# Proiect2026Hagi.net
KiCad netlist of a schematic drawn in EAGLE
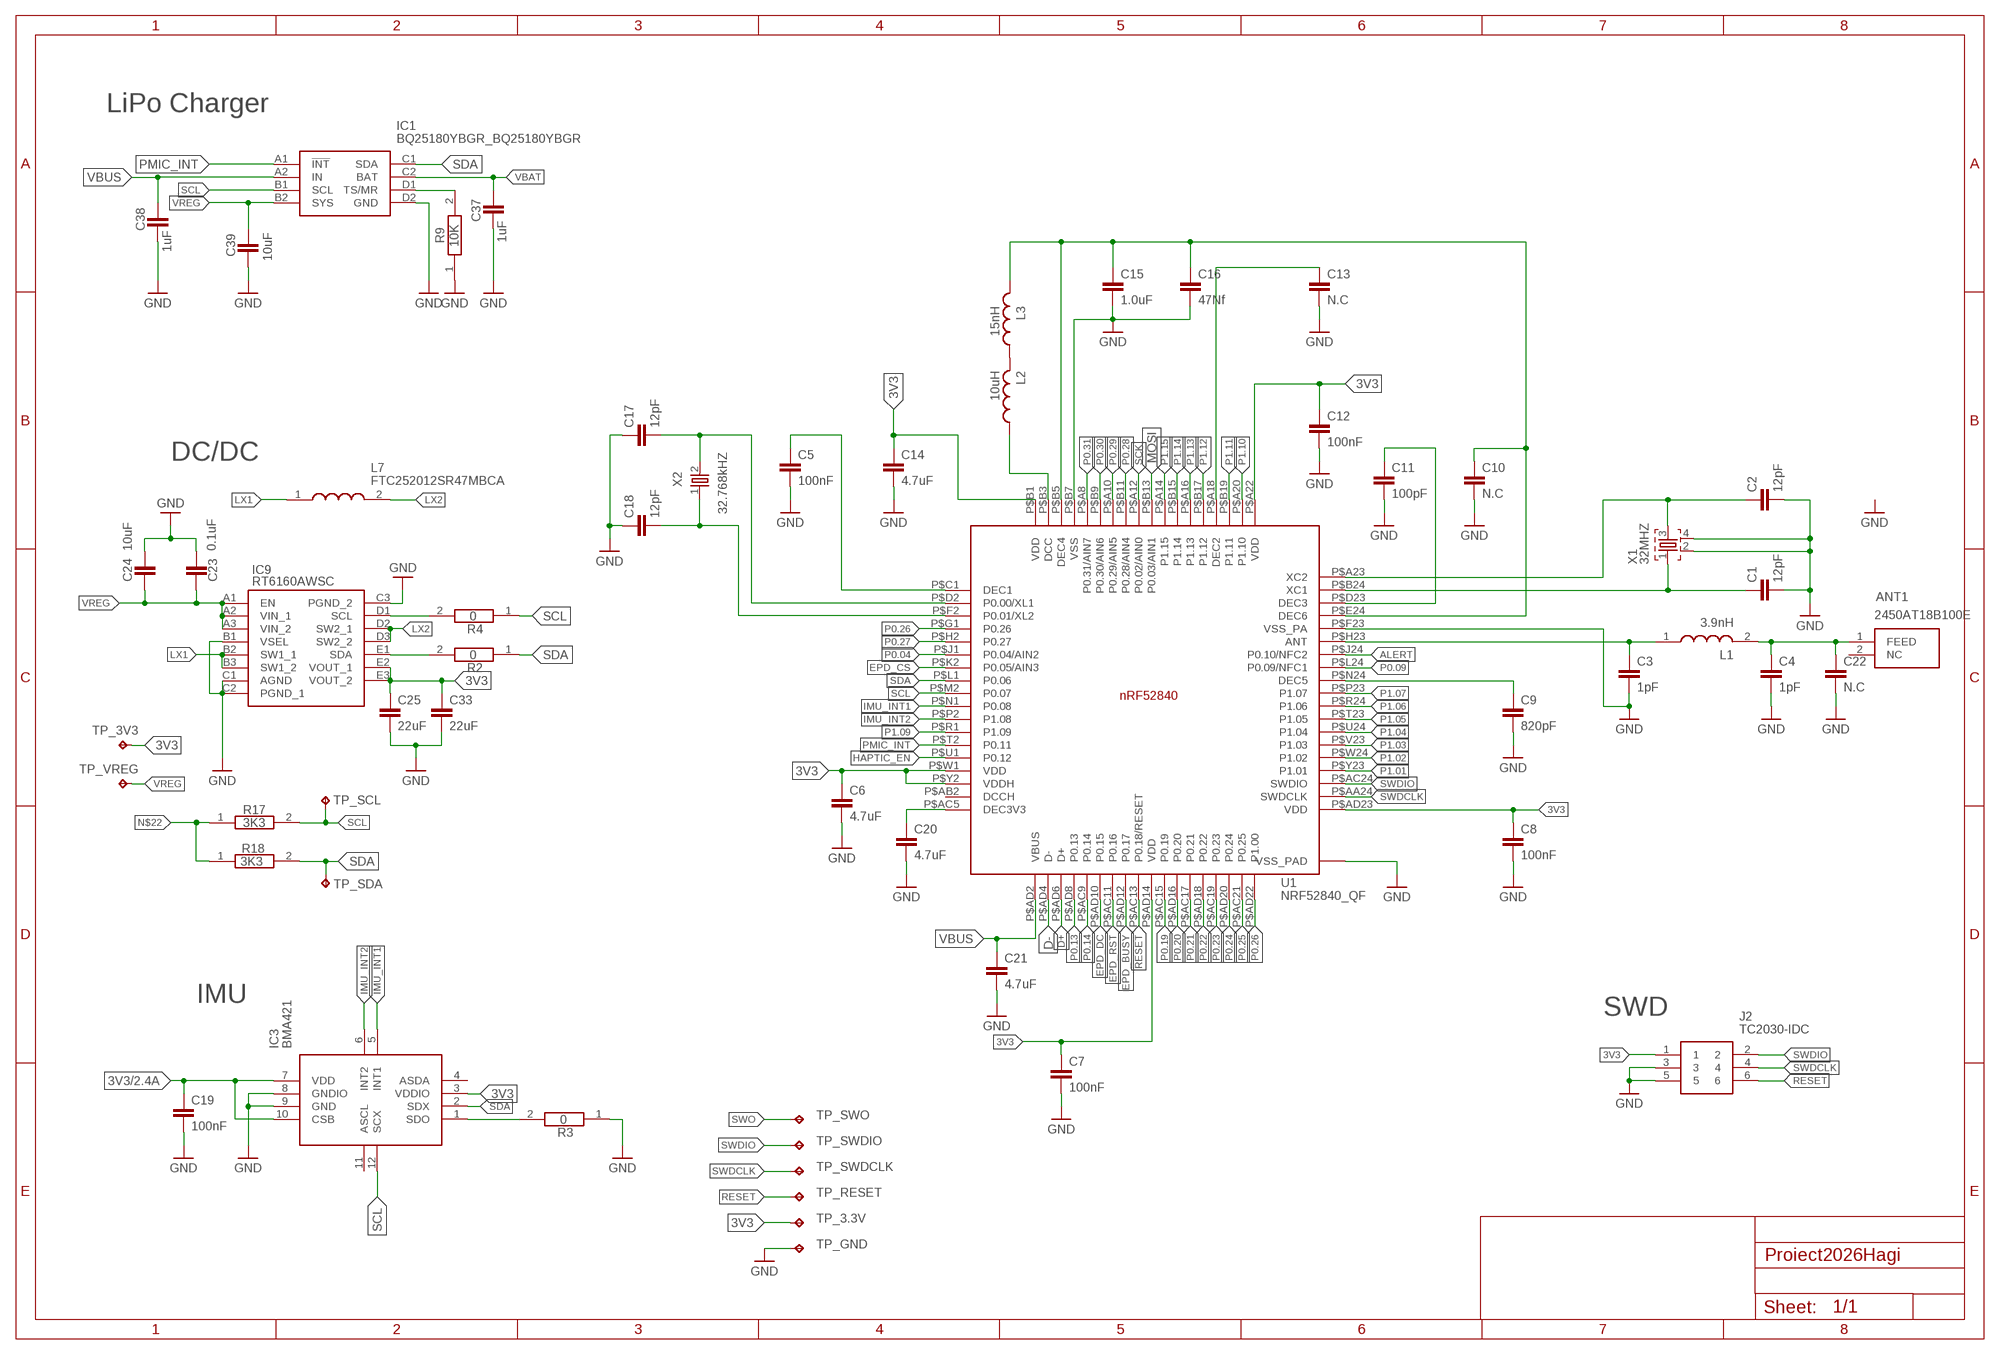
[diagram p0: schematic, sheet 1, part 1 of 2]
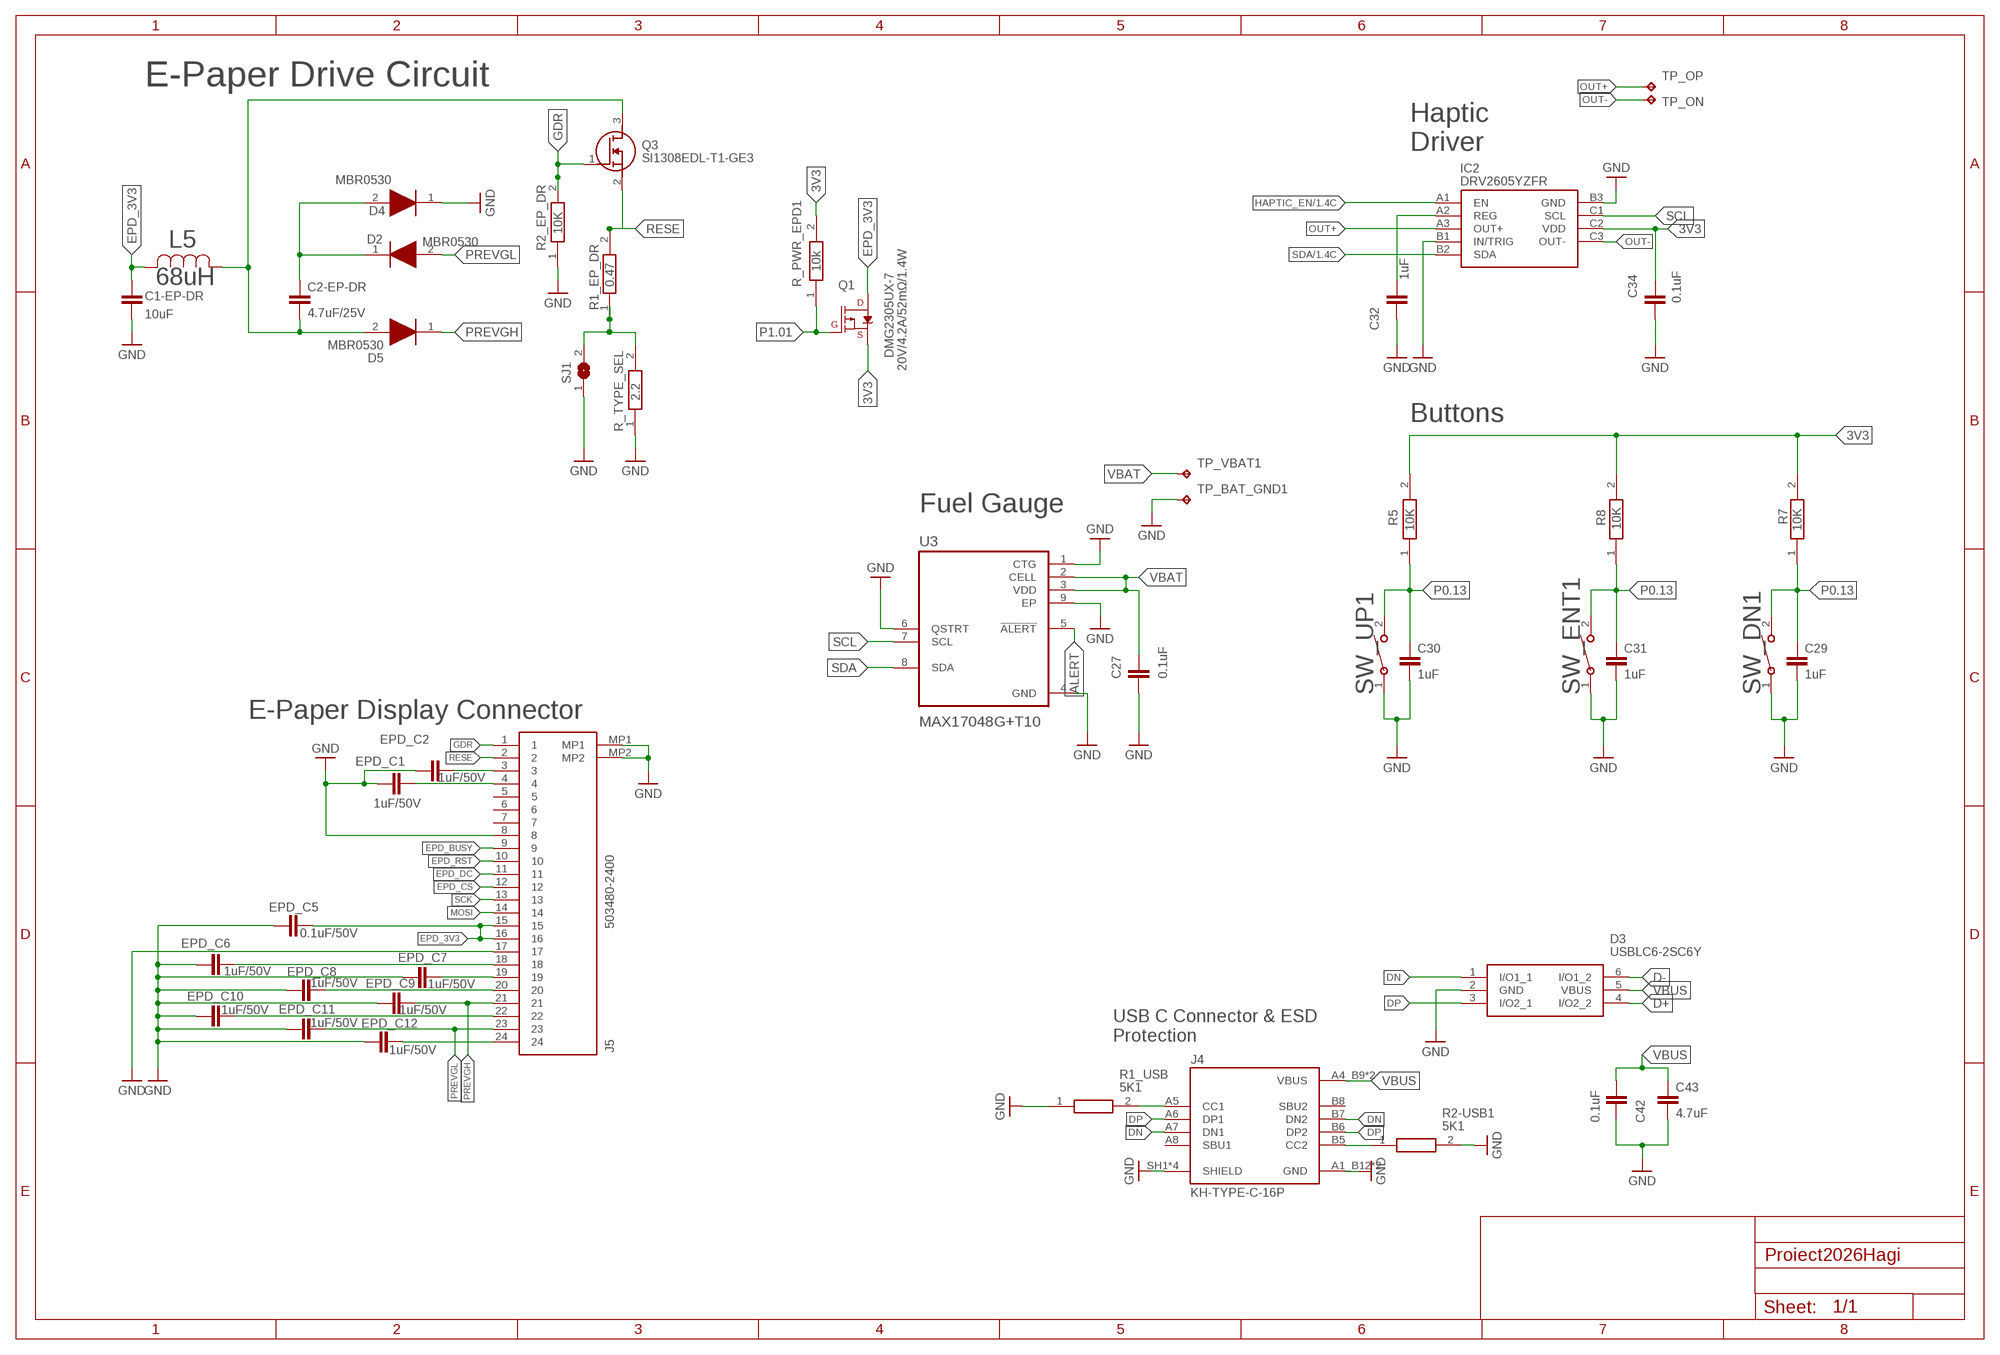
[diagram p1: schematic, sheet 1, part 2 of 2]

(export (version "E")
  (design (tool "Eeschema 10.0.6"))
  (components
    (comp (ref "ANT1")
      (value "2450AT18B100E")
      (footprint "eagle-import:2450AT18B100E_ANTC3216X140N")
      (fields (field (name "MOUSER_PART_NUMBER") "609-2450AT18B100E"))
      (libsource (lib "eagle-import") (part "2450AT18B100E_2450AT18B100E"))
    )
    (comp (ref "C1")
      (value "12pF")
      (footprint "eagle-import:NORDIC_NRF_3_RESC0201_L")
      (libsource (lib "eagle-import") (part "NORDIC_NRF_3_CAPACITOR_0201_L"))
    )
    (comp (ref "C1-EP-DR")
      (value "10uF")
      (footprint "eagle-import:NORDIC_NRF_3_RESC0402_L")
      (libsource (lib "eagle-import") (part "NORDIC_NRF_3_CAPACITOR_0402_L"))
    )
    (comp (ref "C2")
      (value "12pF")
      (footprint "eagle-import:NORDIC_NRF_3_RESC0201_L")
      (libsource (lib "eagle-import") (part "NORDIC_NRF_3_CAPACITOR_0201_L"))
    )
    (comp (ref "C2-EP-DR")
      (value "4.7uF/25V")
      (footprint "eagle-import:NORDIC_NRF_3_RESC0402_L")
      (libsource (lib "eagle-import") (part "NORDIC_NRF_3_CAPACITOR_0402_L"))
    )
    (comp (ref "C3")
      (value "1pF")
      (footprint "eagle-import:NORDIC_NRF_3_RESC0201_L")
      (libsource (lib "eagle-import") (part "NORDIC_NRF_3_CAPACITOR_0201_L"))
    )
    (comp (ref "C4")
      (value "1pF")
      (footprint "eagle-import:NORDIC_NRF_3_RESC0201_L")
      (libsource (lib "eagle-import") (part "NORDIC_NRF_3_CAPACITOR_0201_L"))
    )
    (comp (ref "C5")
      (value "100nF")
      (footprint "eagle-import:NORDIC_NRF_3_RESC0201_L")
      (libsource (lib "eagle-import") (part "NORDIC_NRF_3_CAPACITOR_0201_L"))
    )
    (comp (ref "C6")
      (value "4.7uF")
      (footprint "eagle-import:NORDIC_NRF_3_RESC0402_L")
      (libsource (lib "eagle-import") (part "NORDIC_NRF_3_CAPACITOR_0402_L"))
    )
    (comp (ref "C7")
      (value "100nF")
      (footprint "eagle-import:NORDIC_NRF_3_RESC0201_L")
      (libsource (lib "eagle-import") (part "NORDIC_NRF_3_CAPACITOR_0201_L"))
    )
    (comp (ref "C8")
      (value "100nF")
      (footprint "eagle-import:NORDIC_NRF_3_RESC0201_L")
      (libsource (lib "eagle-import") (part "NORDIC_NRF_3_CAPACITOR_0201_L"))
    )
    (comp (ref "C9")
      (value "820pF")
      (footprint "eagle-import:NORDIC_NRF_3_RESC0201_L")
      (libsource (lib "eagle-import") (part "NORDIC_NRF_3_CAPACITOR_0201_L"))
    )
    (comp (ref "C10")
      (value "N.C")
      (footprint "eagle-import:NORDIC_NRF_3_RESC0201_L")
      (libsource (lib "eagle-import") (part "NORDIC_NRF_3_CAPACITOR_0201_L"))
    )
    (comp (ref "C11")
      (value "100pF")
      (footprint "eagle-import:NORDIC_NRF_3_RESC0201_L")
      (libsource (lib "eagle-import") (part "NORDIC_NRF_3_CAPACITOR_0201_L"))
    )
    (comp (ref "C12")
      (value "100nF")
      (footprint "eagle-import:NORDIC_NRF_3_RESC0201_L")
      (libsource (lib "eagle-import") (part "NORDIC_NRF_3_CAPACITOR_0201_L"))
    )
    (comp (ref "C13")
      (value "N.C")
      (footprint "eagle-import:NORDIC_NRF_3_RESC0201_L")
      (libsource (lib "eagle-import") (part "NORDIC_NRF_3_CAPACITOR_0201_L"))
    )
    (comp (ref "C14")
      (value "4.7uF")
      (footprint "eagle-import:NORDIC_NRF_3_RESC0402_L")
      (libsource (lib "eagle-import") (part "NORDIC_NRF_3_CAPACITOR_0402_L"))
    )
    (comp (ref "C15")
      (value "1.0uF")
      (footprint "eagle-import:NORDIC_NRF_3_RESC0402_L")
      (libsource (lib "eagle-import") (part "NORDIC_NRF_3_CAPACITOR_0402_L"))
    )
    (comp (ref "C16")
      (value "47Nf")
      (footprint "eagle-import:NORDIC_NRF_3_RESC0201_L")
      (libsource (lib "eagle-import") (part "NORDIC_NRF_3_CAPACITOR_0201_L"))
    )
    (comp (ref "C17")
      (value "12pF")
      (footprint "eagle-import:NORDIC_NRF_3_RESC0201_L")
      (libsource (lib "eagle-import") (part "NORDIC_NRF_3_CAPACITOR_0201_L"))
    )
    (comp (ref "C18")
      (value "12pF")
      (footprint "eagle-import:NORDIC_NRF_3_RESC0201_L")
      (libsource (lib "eagle-import") (part "NORDIC_NRF_3_CAPACITOR_0201_L"))
    )
    (comp (ref "C19")
      (value "100nF")
      (footprint "eagle-import:NORDIC_NRF_3_RESC0201_L")
      (libsource (lib "eagle-import") (part "NORDIC_NRF_3_CAPACITOR_0201_L"))
    )
    (comp (ref "C20")
      (value "4.7uF")
      (footprint "eagle-import:NORDIC_NRF_3_RESC0402_L")
      (libsource (lib "eagle-import") (part "NORDIC_NRF_3_CAPACITOR_0402_L"))
    )
    (comp (ref "C21")
      (value "4.7uF")
      (footprint "eagle-import:NORDIC_NRF_3_RESC0402_L")
      (libsource (lib "eagle-import") (part "NORDIC_NRF_3_CAPACITOR_0402_L"))
    )
    (comp (ref "C22")
      (value "N.C")
      (footprint "eagle-import:NORDIC_NRF_3_RESC0201_L")
      (libsource (lib "eagle-import") (part "NORDIC_NRF_3_CAPACITOR_0201_L"))
    )
    (comp (ref "C23")
      (value "0.1uF")
      (footprint "eagle-import:NORDIC_NRF_3_RESC0402_L")
      (libsource (lib "eagle-import") (part "NORDIC_NRF_3_CAPACITOR_0402_L"))
    )
    (comp (ref "C24")
      (value "10uF")
      (footprint "eagle-import:NORDIC_NRF_3_RESC0201_L")
      (libsource (lib "eagle-import") (part "NORDIC_NRF_3_CAPACITOR_0201_L"))
    )
    (comp (ref "C25")
      (value "22uF")
      (footprint "eagle-import:NORDIC_NRF_3_RESC0402_L")
      (libsource (lib "eagle-import") (part "NORDIC_NRF_3_CAPACITOR_0402_L"))
    )
    (comp (ref "C27")
      (value "0.1uF")
      (footprint "eagle-import:NORDIC_NRF_3_RESC0201_L")
      (libsource (lib "eagle-import") (part "NORDIC_NRF_3_CAPACITOR_0201_L"))
    )
    (comp (ref "C29")
      (value "1uF")
      (footprint "eagle-import:NORDIC_NRF_3_RESC0402_L")
      (libsource (lib "eagle-import") (part "NORDIC_NRF_3_CAPACITOR_0402_L"))
    )
    (comp (ref "C30")
      (value "1uF")
      (footprint "eagle-import:NORDIC_NRF_3_RESC0402_L")
      (libsource (lib "eagle-import") (part "NORDIC_NRF_3_CAPACITOR_0402_L"))
    )
    (comp (ref "C31")
      (value "1uF")
      (footprint "eagle-import:NORDIC_NRF_3_RESC0402_L")
      (libsource (lib "eagle-import") (part "NORDIC_NRF_3_CAPACITOR_0402_L"))
    )
    (comp (ref "C32")
      (value "1uF")
      (footprint "eagle-import:NORDIC_NRF_3_RESC0402_L")
      (libsource (lib "eagle-import") (part "NORDIC_NRF_3_CAPACITOR_0402_L"))
    )
    (comp (ref "C33")
      (value "22uF")
      (footprint "eagle-import:NORDIC_NRF_3_RESC0402_L")
      (libsource (lib "eagle-import") (part "NORDIC_NRF_3_CAPACITOR_0402_L"))
    )
    (comp (ref "C34")
      (value "0.1uF")
      (footprint "eagle-import:NORDIC_NRF_3_RESC0201_L")
      (libsource (lib "eagle-import") (part "NORDIC_NRF_3_CAPACITOR_0201_L"))
    )
    (comp (ref "C37")
      (value "1uF")
      (footprint "eagle-import:PERFECT_0402_0402")
      (libsource (lib "eagle-import") (part "PERFECT_0402_CAP_0402"))
    )
    (comp (ref "C38")
      (value "1uF")
      (footprint "eagle-import:PERFECT_0402_0402")
      (libsource (lib "eagle-import") (part "PERFECT_0402_CAP_0402"))
    )
    (comp (ref "C39")
      (value "10uF")
      (footprint "eagle-import:PERFECT_0402_0402")
      (libsource (lib "eagle-import") (part "PERFECT_0402_CAP_0402"))
    )
    (comp (ref "C42")
      (value "0.1uF")
      (footprint "eagle-import:NORDIC_NRF_3_RESC0201_L")
      (libsource (lib "eagle-import") (part "NORDIC_NRF_3_CAPACITOR_0201_L"))
    )
    (comp (ref "C43")
      (value "4.7uF")
      (footprint "eagle-import:NORDIC_NRF_3_RESC0402_L")
      (libsource (lib "eagle-import") (part "NORDIC_NRF_3_CAPACITOR_0402_L"))
    )
    (comp (ref "D2")
      (value "MBR0530")
      (footprint "eagle-import:ESP32_C6_LIBRARY_5_SOD3716X135N")
      (fields (field (name "MF") "ON Semiconductor"))
      (libsource (lib "eagle-import") (part "ESP32_C6_LIBRARY_5_MBR0530"))
    )
    (comp (ref "D3")
      (value "USBLC6-2SC6Y")
      (footprint "eagle-import:ESP32_C6_LIBRARY_3_SOT95P280X145-6N")
      (fields (field (name "MF") "STMicroelectronics"))
      (libsource (lib "eagle-import") (part "ESP32_C6_LIBRARY_3_USBLC6-2SC6Y"))
    )
    (comp (ref "D4")
      (value "MBR0530")
      (footprint "eagle-import:ESP32_C6_LIBRARY_5_SOD3716X135N")
      (fields (field (name "MF") "ON Semiconductor"))
      (libsource (lib "eagle-import") (part "ESP32_C6_LIBRARY_5_MBR0530"))
    )
    (comp (ref "D5")
      (value "MBR0530")
      (footprint "eagle-import:ESP32_C6_LIBRARY_5_SOD3716X135N")
      (fields (field (name "MF") "ON Semiconductor"))
      (libsource (lib "eagle-import") (part "ESP32_C6_LIBRARY_5_MBR0530"))
    )
    (comp (ref "EPD_C1")
      (value "1uF/50V")
      (footprint "eagle-import:NORDIC_NRF_3_RESC0402_L")
      (libsource (lib "eagle-import") (part "NORDIC_NRF_3_CAPACITOR_0402_L"))
    )
    (comp (ref "EPD_C2")
      (value "1uF/50V")
      (footprint "eagle-import:NORDIC_NRF_3_RESC0402_L")
      (libsource (lib "eagle-import") (part "NORDIC_NRF_3_CAPACITOR_0402_L"))
    )
    (comp (ref "EPD_C5")
      (value "0.1uF/50V")
      (footprint "eagle-import:NORDIC_NRF_3_RESC0201_L")
      (libsource (lib "eagle-import") (part "NORDIC_NRF_3_CAPACITOR_0201_L"))
    )
    (comp (ref "EPD_C6")
      (value "1uF/50V")
      (footprint "eagle-import:NORDIC_NRF_3_RESC0402_L")
      (libsource (lib "eagle-import") (part "NORDIC_NRF_3_CAPACITOR_0402_L"))
    )
    (comp (ref "EPD_C7")
      (value "1uF/50V")
      (footprint "eagle-import:NORDIC_NRF_3_RESC0402_L")
      (libsource (lib "eagle-import") (part "NORDIC_NRF_3_CAPACITOR_0402_L"))
    )
    (comp (ref "EPD_C8")
      (value "1uF/50V")
      (footprint "eagle-import:NORDIC_NRF_3_RESC0402_L")
      (libsource (lib "eagle-import") (part "NORDIC_NRF_3_CAPACITOR_0402_L"))
    )
    (comp (ref "EPD_C9")
      (value "1uF/50V")
      (footprint "eagle-import:NORDIC_NRF_3_RESC0402_L")
      (libsource (lib "eagle-import") (part "NORDIC_NRF_3_CAPACITOR_0402_L"))
    )
    (comp (ref "EPD_C10")
      (value "1uF/50V")
      (footprint "eagle-import:NORDIC_NRF_3_RESC0402_L")
      (libsource (lib "eagle-import") (part "NORDIC_NRF_3_CAPACITOR_0402_L"))
    )
    (comp (ref "EPD_C11")
      (value "1uF/50V")
      (footprint "eagle-import:NORDIC_NRF_3_RESC0402_L")
      (libsource (lib "eagle-import") (part "NORDIC_NRF_3_CAPACITOR_0402_L"))
    )
    (comp (ref "EPD_C12")
      (value "1uF/50V")
      (footprint "eagle-import:NORDIC_NRF_3_RESC0402_L")
      (libsource (lib "eagle-import") (part "NORDIC_NRF_3_CAPACITOR_0402_L"))
    )
    (comp (ref "IC1")
      (value "BQ25180YBGR_BQ25180YBGR")
      (footprint "eagle-import:BQ25180YBGR_BGA8C40P2X4_100X155X50")
      (fields
        (field (name "ARROW_PART_NUMBER") "BQ25180YBGR")
        (field (name "MOUSER_PART_NUMBER") "595-BQ25180YBGR")
      )
      (libsource (lib "eagle-import") (part "BQ25180YBGR_BQ25180YBGR"))
    )
    (comp (ref "IC2")
      (value "DRV2605YZFR")
      (footprint "eagle-import:DRV2605YZFR_BGA9C50P3X3_144X144X62")
      (libsource (lib "eagle-import") (part "DRV2605YZFR_DRV2605YZFR"))
    )
    (comp (ref "IC3")
      (value "BMA421")
      (footprint "eagle-import:BMA423_BMA423")
      (fields (field (name "ARROW_PART_NUMBER") "BMA423") (field (name "MOUSER_PART_NUMBER") "262-BMA423"))
      (libsource (lib "eagle-import") (part "BMA423_BMA423"))
    )
    (comp (ref "IC9")
      (value "RT6160AWSC")
      (footprint "eagle-import:RT6160AWSC_BGA15C40P3X5_140X230X60")
      (fields (field (name "MOUSER_PART_NUMBER") "835-RT6160AWSC"))
      (libsource (lib "eagle-import") (part "RT6160AWSC_RT6160AWSC"))
    )
    (comp (ref "J2")
      (value "TC2030-IDC")
      (footprint "eagle-import:TC2030-IDC_TC2030IDC")
      (libsource (lib "eagle-import") (part "TC2030-IDC_TC2030-IDC"))
    )
    (comp (ref "J4")
      (value "KH-TYPE-C-16P")
      (footprint "eagle-import:KH-TYPE-C-16P_KINGHELM_KH-TYPE-C-16P")
      (fields (field (name "MF") "kinghelm"))
      (libsource (lib "eagle-import") (part "KH-TYPE-C-16P_KH-TYPE-C-16P"))
    )
    (comp (ref "J5")
      (value "503480-2400")
      (footprint "eagle-import:503480-2400_5034802400")
      (fields (field (name "MOUSER_PART_NUMBER") "538-503480-2400"))
      (libsource (lib "eagle-import") (part "503480-2400_503480-2400"))
    )
    (comp (ref "L1")
      (value "3.9nH")
      (footprint "eagle-import:MLP2016SR47MT0S1_INDC2016X100N")
      (fields (field (name "MANUFACTURER_PART_NUMBER") "FTC252012SR47MBCA"))
      (libsource (lib "eagle-import") (part "MLP2016SR47MT0S1_FTC252012SR47MBCA"))
    )
    (comp (ref "L2")
      (value "10uH")
      (footprint "eagle-import:NORDIC_NRF_2_RESC0402_L")
      (libsource (lib "eagle-import") (part "NORDIC_NRF_2_INDUCTOR_0402_L"))
    )
    (comp (ref "L3")
      (value "15nH")
      (footprint "eagle-import:NORDIC_NRF_2_RESC0402_L")
      (libsource (lib "eagle-import") (part "NORDIC_NRF_2_INDUCTOR_0402_L"))
    )
    (comp (ref "L5")
      (value "68uH")
      (footprint "eagle-import:ESP32_C6_LIBRARY_2_IND_4828-WE-TPC_WRE")
      (fields
        (field (name "MANUFACTURER_PART_NUMBER") "744043680")
        (field (name "COPYRIGHT") "Copyright (C) 2024 Ultra Librarian. All rights reserved.")
      )
      (libsource (lib "eagle-import") (part "ESP32_C6_LIBRARY_2_744043680IND_4828-WE-TPC_WRE"))
    )
    (comp (ref "L7")
      (value "FTC252012SR47MBCA")
      (footprint "eagle-import:MLP2016SR47MT0S1_INDC2016X100N")
      (libsource (lib "eagle-import") (part "MLP2016SR47MT0S1_FTC252012SR47MBCA"))
    )
    (comp (ref "Q1")
      (value "20V/4.2A/52mΩ/1.4W")
      (footprint "eagle-import:ESP32_C6_LIBRARY_4_ESP32_C6_LIBRARY_4_ESP32_C6_LIBRARY_4_ESP32_C6_LIBRARY_4_ESP32_WROVER_SPARKFUN-DISCRETESEMI_SOT23-3")
      (libsource (lib "eagle-import") (part "ESP32_C6_LIBRARY_4_ESP32_WROVER_SPARKFUN-DISCRETESEMI_MOSFET_PCH-DMG2305UX-7"))
    )
    (comp (ref "Q3")
      (value "SI1308EDL-T1-GE3")
      (footprint "eagle-import:ESP32_C6_LIBRARY_6_SOT65P210X110-3N")
      (fields (field (name "MF") "Vishay Siliconix"))
      (libsource (lib "eagle-import") (part "ESP32_C6_LIBRARY_6_SI1308EDL-T1-GE3"))
    )
    (comp (ref "R1_EP_DR")
      (value "0.47")
      (footprint "eagle-import:CPF0201D7K68C1_0201")
      (libsource (lib "eagle-import") (part "CPF0201D7K68C1_CPF0201D7K68C1"))
    )
    (comp (ref "R1_USB")
      (value "5K1")
      (footprint "eagle-import:CPF0201D7K68C1_0201")
      (libsource (lib "eagle-import") (part "CPF0201D7K68C1_CPF0201D7K68C1"))
    )
    (comp (ref "R2")
      (value "0")
      (footprint "eagle-import:CPF0201D7K68C1_0201")
      (libsource (lib "eagle-import") (part "CPF0201D7K68C1_CPF0201D7K68C1"))
    )
    (comp (ref "R2-USB1")
      (value "5K1")
      (footprint "eagle-import:CPF0201D7K68C1_0201")
      (libsource (lib "eagle-import") (part "CPF0201D7K68C1_CPF0201D7K68C1"))
    )
    (comp (ref "R2_EP_DR")
      (value "10K")
      (footprint "eagle-import:CPF0201D7K68C1_0201")
      (libsource (lib "eagle-import") (part "CPF0201D7K68C1_CPF0201D7K68C1"))
    )
    (comp (ref "R3")
      (value "0")
      (footprint "eagle-import:CPF0201D7K68C1_0201")
      (libsource (lib "eagle-import") (part "CPF0201D7K68C1_CPF0201D7K68C1"))
    )
    (comp (ref "R4")
      (value "0")
      (footprint "eagle-import:CPF0201D7K68C1_0201")
      (libsource (lib "eagle-import") (part "CPF0201D7K68C1_CPF0201D7K68C1"))
    )
    (comp (ref "R5")
      (value "10K")
      (footprint "eagle-import:CPF0201D7K68C1_0201")
      (libsource (lib "eagle-import") (part "CPF0201D7K68C1_CPF0201D7K68C1"))
    )
    (comp (ref "R7")
      (value "10K")
      (footprint "eagle-import:CPF0201D7K68C1_0201")
      (libsource (lib "eagle-import") (part "CPF0201D7K68C1_CPF0201D7K68C1"))
    )
    (comp (ref "R8")
      (value "10K")
      (footprint "eagle-import:CPF0201D7K68C1_0201")
      (libsource (lib "eagle-import") (part "CPF0201D7K68C1_CPF0201D7K68C1"))
    )
    (comp (ref "R9")
      (value "10K")
      (footprint "eagle-import:CPF0201D7K68C1_0201")
      (libsource (lib "eagle-import") (part "CPF0201D7K68C1_CPF0201D7K68C1"))
    )
    (comp (ref "R17")
      (value "3K3")
      (footprint "eagle-import:CPF0201D7K68C1_0201")
      (libsource (lib "eagle-import") (part "CPF0201D7K68C1_CPF0201D7K68C1"))
    )
    (comp (ref "R18")
      (value "3K3")
      (footprint "eagle-import:CPF0201D7K68C1_0201")
      (libsource (lib "eagle-import") (part "CPF0201D7K68C1_CPF0201D7K68C1"))
    )
    (comp (ref "R_PWR_EPD1")
      (value "10k")
      (footprint "eagle-import:CPF0201D7K68C1_0201")
      (libsource (lib "eagle-import") (part "CPF0201D7K68C1_CPF0201D7K68C1"))
    )
    (comp (ref "R_TYPE_SEL")
      (value "2.2")
      (footprint "eagle-import:CPF0201D7K68C1_0201")
      (libsource (lib "eagle-import") (part "CPF0201D7K68C1_CPF0201D7K68C1"))
    )
    (comp (ref "SJ1")
      (value "ESP32_C6_LIBRARY_7_JUMPER_SJ")
      (footprint "eagle-import:ESP32_C6_LIBRARY_7_JUMPER_SJ")
      (libsource (lib "eagle-import") (part "ESP32_C6_LIBRARY_7_JUMPER_SJ"))
    )
    (comp (ref "SW_DN1")
      (value "2025-10-22_07-23-44_LIBRARY_EVP-AKE31ASW_EVP-AKE31A_PAN")
      (footprint "eagle-import:2025-10-22_07-23-44_LIBRARY_SW_EVP-AKE31A_PAN")
      (fields
        (field (name "MANUFACTURER_PART_NUMBER") "EVP-AKE31A")
        (field (name "COPYRIGHT") "Copyright (C) 2025 Ultra Librarian. All rights reserved.")
      )
      (libsource (lib "eagle-import") (part "2025-10-22_07-23-44_LIBRARY_EVP-AKE31ASW_EVP-AKE31A_PAN"))
    )
    (comp (ref "SW_ENT1")
      (value "2025-10-22_07-23-44_LIBRARY_EVP-AKE31ASW_EVP-AKE31A_PAN")
      (footprint "eagle-import:2025-10-22_07-23-44_LIBRARY_SW_EVP-AKE31A_PAN")
      (fields
        (field (name "MANUFACTURER_PART_NUMBER") "EVP-AKE31A")
        (field (name "COPYRIGHT") "Copyright (C) 2025 Ultra Librarian. All rights reserved.")
      )
      (libsource (lib "eagle-import") (part "2025-10-22_07-23-44_LIBRARY_EVP-AKE31ASW_EVP-AKE31A_PAN"))
    )
    (comp (ref "SW_UP1")
      (value "2025-10-22_07-23-44_LIBRARY_EVP-AKE31ASW_EVP-AKE31A_PAN")
      (footprint "eagle-import:2025-10-22_07-23-44_LIBRARY_SW_EVP-AKE31A_PAN")
      (fields
        (field (name "MANUFACTURER_PART_NUMBER") "EVP-AKE31A")
        (field (name "COPYRIGHT") "Copyright (C) 2025 Ultra Librarian. All rights reserved.")
      )
      (libsource (lib "eagle-import") (part "2025-10-22_07-23-44_LIBRARY_EVP-AKE31ASW_EVP-AKE31A_PAN"))
    )
    (comp (ref "TP_3.3V")
      (value "HECTOR_WATCH_1_TPTP20R")
      (footprint "eagle-import:HECTOR_WATCH_1_TP20R")
      (libsource (lib "eagle-import") (part "HECTOR_WATCH_1_TPTP20R"))
    )
    (comp (ref "TP_3V3")
      (value "HECTOR_WATCH_1_TPTP20R")
      (footprint "eagle-import:HECTOR_WATCH_1_TP20R")
      (libsource (lib "eagle-import") (part "HECTOR_WATCH_1_TPTP20R"))
    )
    (comp (ref "TP_BAT_GND1")
      (value "HECTOR_WATCH_1_TPTP20R")
      (footprint "eagle-import:HECTOR_WATCH_1_TP20R")
      (libsource (lib "eagle-import") (part "HECTOR_WATCH_1_TPTP20R"))
    )
    (comp (ref "TP_GND")
      (value "HECTOR_WATCH_1_TPTP20R")
      (footprint "eagle-import:HECTOR_WATCH_1_TP20R")
      (libsource (lib "eagle-import") (part "HECTOR_WATCH_1_TPTP20R"))
    )
    (comp (ref "TP_ON")
      (value "HECTOR_WATCH_1_TPTP20R")
      (footprint "eagle-import:HECTOR_WATCH_1_TP20R")
      (libsource (lib "eagle-import") (part "HECTOR_WATCH_1_TPTP20R"))
    )
    (comp (ref "TP_OP")
      (value "HECTOR_WATCH_1_TPTP20R")
      (footprint "eagle-import:HECTOR_WATCH_1_TP20R")
      (libsource (lib "eagle-import") (part "HECTOR_WATCH_1_TPTP20R"))
    )
    (comp (ref "TP_RESET")
      (value "HECTOR_WATCH_1_TPTP20R")
      (footprint "eagle-import:HECTOR_WATCH_1_TP20R")
      (libsource (lib "eagle-import") (part "HECTOR_WATCH_1_TPTP20R"))
    )
    (comp (ref "TP_SCL")
      (value "HECTOR_WATCH_1_TPTP20R")
      (footprint "eagle-import:HECTOR_WATCH_1_TP20R")
      (libsource (lib "eagle-import") (part "HECTOR_WATCH_1_TPTP20R"))
    )
    (comp (ref "TP_SDA")
      (value "HECTOR_WATCH_1_TPTP20R")
      (footprint "eagle-import:HECTOR_WATCH_1_TP20R")
      (libsource (lib "eagle-import") (part "HECTOR_WATCH_1_TPTP20R"))
    )
    (comp (ref "TP_SWDCLK")
      (value "HECTOR_WATCH_1_TPTP20R")
      (footprint "eagle-import:HECTOR_WATCH_1_TP20R")
      (libsource (lib "eagle-import") (part "HECTOR_WATCH_1_TPTP20R"))
    )
    (comp (ref "TP_SWDIO")
      (value "HECTOR_WATCH_1_TPTP20R")
      (footprint "eagle-import:HECTOR_WATCH_1_TP20R")
      (libsource (lib "eagle-import") (part "HECTOR_WATCH_1_TPTP20R"))
    )
    (comp (ref "TP_SWO")
      (value "HECTOR_WATCH_1_TPTP20R")
      (footprint "eagle-import:HECTOR_WATCH_1_TP20R")
      (libsource (lib "eagle-import") (part "HECTOR_WATCH_1_TPTP20R"))
    )
    (comp (ref "TP_VBAT1")
      (value "HECTOR_WATCH_1_TPTP20R")
      (footprint "eagle-import:HECTOR_WATCH_1_TP20R")
      (libsource (lib "eagle-import") (part "HECTOR_WATCH_1_TPTP20R"))
    )
    (comp (ref "TP_VREG")
      (value "HECTOR_WATCH_1_TPTP20R")
      (footprint "eagle-import:HECTOR_WATCH_1_TP20R")
      (libsource (lib "eagle-import") (part "HECTOR_WATCH_1_TPTP20R"))
    )
    (comp (ref "U1")
      (value "NRF52840_QF")
      (footprint "eagle-import:NORDIC_NRF_4_AQFN50P700X700X85_HS-74N")
      (libsource (lib "eagle-import") (part "NORDIC_NRF_4_NRF52840_QF"))
    )
    (comp (ref "U3")
      (value "MAX17048G+T10")
      (footprint "eagle-import:ESP32_C6_LIBRARY_SON50P200X200X80-9N")
      (fields (field (name "MF") "Analog Devices"))
      (libsource (lib "eagle-import") (part "ESP32_C6_LIBRARY_MAX17048G+T10"))
    )
    (comp (ref "X1")
      (value "32MHZ")
      (footprint "eagle-import:NORDIC_NRF_BT-XTAL_2016_N")
      (libsource (lib "eagle-import") (part "NORDIC_NRF_XTAL_32MHZ"))
    )
    (comp (ref "X2")
      (value "32.768kHZ")
      (footprint "eagle-import:NORDIC_NRF_1_XTAL_3215_N")
      (libsource (lib "eagle-import") (part "NORDIC_NRF_1_XTAL_32KHZ"))
    )
  )
  (nets
    (net (code "1") (name "3V3") (class "Default")
      (node (ref "C12") (pin "1") (pinfunction "1_1") (pintype "passive"))
      (node (ref "C14") (pin "1") (pinfunction "1_1") (pintype "passive"))
      (node (ref "C25") (pin "1") (pinfunction "1_1") (pintype "passive"))
      (node (ref "C33") (pin "1") (pinfunction "1_1") (pintype "passive"))
      (node (ref "C34") (pin "1") (pinfunction "1_1") (pintype "passive"))
      (node (ref "C6") (pin "1") (pinfunction "1_1") (pintype "passive"))
      (node (ref "C7") (pin "1") (pinfunction "1_1") (pintype "passive"))
      (node (ref "C8") (pin "1") (pinfunction "1_1") (pintype "passive"))
      (node (ref "IC2") (pin "C2") (pinfunction "VDD_C2") (pintype "bidirectional"))
      (node (ref "IC3") (pin "3") (pinfunction "VDDIO_3") (pintype "bidirectional"))
      (node (ref "IC9") (pin "E2") (pinfunction "VOUT_1_E2") (pintype "bidirectional"))
      (node (ref "IC9") (pin "E3") (pinfunction "VOUT_2_E3") (pintype "bidirectional"))
      (node (ref "J2") (pin "1") (pinfunction "1_1") (pintype "bidirectional"))
      (node (ref "Q1") (pin "2") (pinfunction "S_2") (pintype "bidirectional"))
      (node (ref "R5") (pin "2") (pinfunction "2_2") (pintype "bidirectional"))
      (node (ref "R7") (pin "2") (pinfunction "2_2") (pintype "bidirectional"))
      (node (ref "R8") (pin "2") (pinfunction "2_2") (pintype "bidirectional"))
      (node (ref "R_PWR_EPD1") (pin "2") (pinfunction "2_2") (pintype "bidirectional"))
      (node (ref "TP_3.3V") (pin "TP") (pinfunction "TP_TP") (pintype "input"))
      (node (ref "TP_3V3") (pin "TP") (pinfunction "TP_TP") (pintype "input"))
      (node (ref "U1") (pin "P$A22") (pinfunction "VDD_P$A22") (pintype "power_in"))
      (node (ref "U1") (pin "P$AD14") (pinfunction "VDD_P$AD14") (pintype "power_in"))
      (node (ref "U1") (pin "P$AD23") (pinfunction "VDD_P$AD23") (pintype "power_in"))
      (node (ref "U1") (pin "P$B1") (pinfunction "VDD_P$B1") (pintype "power_in"))
      (node (ref "U1") (pin "P$W1") (pinfunction "VDD_P$W1") (pintype "power_in"))
      (node (ref "U1") (pin "P$Y2") (pinfunction "VDDH_P$Y2") (pintype "power_in"))
    )
    (net (code "2") (name "3V3{slash}2.4A") (class "Default")
      (node (ref "C19") (pin "1") (pinfunction "1_1") (pintype "passive"))
      (node (ref "IC3") (pin "10") (pinfunction "CSB_10") (pintype "bidirectional"))
      (node (ref "IC3") (pin "7") (pinfunction "VDD_7") (pintype "bidirectional"))
    )
    (net (code "3") (name "ALERT") (class "Default")
      (node (ref "U1") (pin "P$J24") (pinfunction "P0.10/NFC2_P$J24") (pintype "bidirectional"))
      (node (ref "U3") (pin "5") (pinfunction "~{ALERT}_5") (pintype "output"))
    )
    (net (code "4") (name "D+") (class "Default")
      (node (ref "D3") (pin "4") (pinfunction "I/O2_2_4") (pintype "bidirectional"))
      (node (ref "U1") (pin "P$AD6") (pinfunction "D+_P$AD6") (pintype "bidirectional"))
    )
    (net (code "5") (name "D-") (class "Default")
      (node (ref "D3") (pin "6") (pinfunction "I/O1_2_6") (pintype "bidirectional"))
      (node (ref "U1") (pin "P$AD4") (pinfunction "D-_P$AD4") (pintype "bidirectional"))
    )
    (net (code "6") (name "DN") (class "Default")
      (node (ref "D3") (pin "1") (pinfunction "I/O1_1_1") (pintype "bidirectional"))
      (node (ref "J4") (pin "A7") (pinfunction "DN1_A7") (pintype "bidirectional"))
      (node (ref "J4") (pin "B7") (pinfunction "DN2_B7") (pintype "bidirectional"))
    )
    (net (code "7") (name "DP") (class "Default")
      (node (ref "D3") (pin "3") (pinfunction "I/O2_1_3") (pintype "bidirectional"))
      (node (ref "J4") (pin "A6") (pinfunction "DP1_A6") (pintype "bidirectional"))
      (node (ref "J4") (pin "B6") (pinfunction "DP2_B6") (pintype "bidirectional"))
    )
    (net (code "8") (name "EPD_3V3") (class "Default")
      (node (ref "C1-EP-DR") (pin "1") (pinfunction "1_1") (pintype "passive"))
      (node (ref "EPD_C5") (pin "2") (pinfunction "2_2") (pintype "passive"))
      (node (ref "J5") (pin "15") (pinfunction "15_15") (pintype "bidirectional"))
      (node (ref "J5") (pin "16") (pinfunction "16_16") (pintype "bidirectional"))
      (node (ref "L5") (pin "2") (pinfunction "2_2") (pintype "passive"))
      (node (ref "Q1") (pin "3") (pinfunction "D_3") (pintype "bidirectional"))
    )
    (net (code "9") (name "EPD_BUSY") (class "Default")
      (node (ref "J5") (pin "9") (pinfunction "9_9") (pintype "bidirectional"))
      (node (ref "U1") (pin "P$AD12") (pinfunction "P0.17_P$AD12") (pintype "bidirectional"))
    )
    (net (code "10") (name "EPD_CS") (class "Default")
      (node (ref "J5") (pin "12") (pinfunction "12_12") (pintype "bidirectional"))
      (node (ref "U1") (pin "P$K2") (pinfunction "P0.05/AIN3_P$K2") (pintype "bidirectional"))
    )
    (net (code "11") (name "EPD_DC") (class "Default")
      (node (ref "J5") (pin "11") (pinfunction "11_11") (pintype "bidirectional"))
      (node (ref "U1") (pin "P$AD10") (pinfunction "P0.15_P$AD10") (pintype "bidirectional"))
    )
    (net (code "12") (name "EPD_RST") (class "Default")
      (node (ref "J5") (pin "10") (pinfunction "10_10") (pintype "bidirectional"))
      (node (ref "U1") (pin "P$AC11") (pinfunction "P0.16_P$AC11") (pintype "bidirectional"))
    )
    (net (code "13") (name "GDR") (class "Default")
      (node (ref "J5") (pin "1") (pinfunction "1_1") (pintype "bidirectional"))
      (node (ref "Q3") (pin "1") (pinfunction "G_1") (pintype "bidirectional"))
      (node (ref "R2_EP_DR") (pin "2") (pinfunction "2_2") (pintype "bidirectional"))
    )
    (net (code "14") (name "GND") (class "Default")
      (node (ref "C1") (pin "2") (pinfunction "2_2") (pintype "passive"))
      (node (ref "C1-EP-DR") (pin "2") (pinfunction "2_2") (pintype "passive"))
      (node (ref "C10") (pin "2") (pinfunction "2_2") (pintype "passive"))
      (node (ref "C11") (pin "2") (pinfunction "2_2") (pintype "passive"))
      (node (ref "C12") (pin "2") (pinfunction "2_2") (pintype "passive"))
      (node (ref "C13") (pin "2") (pinfunction "2_2") (pintype "passive"))
      (node (ref "C14") (pin "2") (pinfunction "2_2") (pintype "passive"))
      (node (ref "C15") (pin "2") (pinfunction "2_2") (pintype "passive"))
      (node (ref "C16") (pin "2") (pinfunction "2_2") (pintype "passive"))
      (node (ref "C17") (pin "1") (pinfunction "1_1") (pintype "passive"))
      (node (ref "C18") (pin "1") (pinfunction "1_1") (pintype "passive"))
      (node (ref "C19") (pin "2") (pinfunction "2_2") (pintype "passive"))
      (node (ref "C2") (pin "2") (pinfunction "2_2") (pintype "passive"))
      (node (ref "C20") (pin "2") (pinfunction "2_2") (pintype "passive"))
      (node (ref "C21") (pin "2") (pinfunction "2_2") (pintype "passive"))
      (node (ref "C22") (pin "2") (pinfunction "2_2") (pintype "passive"))
      (node (ref "C23") (pin "1") (pinfunction "1_1") (pintype "passive"))
      (node (ref "C24") (pin "1") (pinfunction "1_1") (pintype "passive"))
      (node (ref "C25") (pin "2") (pinfunction "2_2") (pintype "passive"))
      (node (ref "C27") (pin "2") (pinfunction "2_2") (pintype "passive"))
      (node (ref "C29") (pin "2") (pinfunction "2_2") (pintype "passive"))
      (node (ref "C3") (pin "2") (pinfunction "2_2") (pintype "passive"))
      (node (ref "C30") (pin "2") (pinfunction "2_2") (pintype "passive"))
      (node (ref "C31") (pin "2") (pinfunction "2_2") (pintype "passive"))
      (node (ref "C32") (pin "2") (pinfunction "2_2") (pintype "passive"))
      (node (ref "C33") (pin "2") (pinfunction "2_2") (pintype "passive"))
      (node (ref "C34") (pin "2") (pinfunction "2_2") (pintype "passive"))
      (node (ref "C37") (pin "2") (pinfunction "2_2") (pintype "passive"))
      (node (ref "C38") (pin "2") (pinfunction "2_2") (pintype "passive"))
      (node (ref "C39") (pin "2") (pinfunction "2_2") (pintype "passive"))
      (node (ref "C4") (pin "2") (pinfunction "2_2") (pintype "passive"))
      (node (ref "C42") (pin "2") (pinfunction "2_2") (pintype "passive"))
      (node (ref "C43") (pin "2") (pinfunction "2_2") (pintype "passive"))
      (node (ref "C5") (pin "2") (pinfunction "2_2") (pintype "passive"))
      (node (ref "C6") (pin "2") (pinfunction "2_2") (pintype "passive"))
      (node (ref "C7") (pin "2") (pinfunction "2_2") (pintype "passive"))
      (node (ref "C8") (pin "2") (pinfunction "2_2") (pintype "passive"))
      (node (ref "C9") (pin "2") (pinfunction "2_2") (pintype "passive"))
      (node (ref "D3") (pin "2") (pinfunction "GND_2") (pintype "bidirectional"))
      (node (ref "D4") (pin "1") (pinfunction "K_1") (pintype "bidirectional"))
      (node (ref "EPD_C1") (pin "1") (pinfunction "1_1") (pintype "passive"))
      (node (ref "EPD_C10") (pin "1") (pinfunction "1_1") (pintype "passive"))
      (node (ref "EPD_C11") (pin "1") (pinfunction "1_1") (pintype "passive"))
      (node (ref "EPD_C12") (pin "1") (pinfunction "1_1") (pintype "passive"))
      (node (ref "EPD_C2") (pin "1") (pinfunction "1_1") (pintype "passive"))
      (node (ref "EPD_C5") (pin "1") (pinfunction "1_1") (pintype "passive"))
      (node (ref "EPD_C6") (pin "1") (pinfunction "1_1") (pintype "passive"))
      (node (ref "EPD_C7") (pin "1") (pinfunction "1_1") (pintype "passive"))
      (node (ref "EPD_C8") (pin "1") (pinfunction "1_1") (pintype "passive"))
      (node (ref "EPD_C9") (pin "1") (pinfunction "1_1") (pintype "passive"))
      (node (ref "IC1") (pin "D2") (pinfunction "GND_D2") (pintype "bidirectional"))
      (node (ref "IC2") (pin "B1") (pinfunction "IN/TRIG_B1") (pintype "bidirectional"))
      (node (ref "IC2") (pin "B3") (pinfunction "GND_B3") (pintype "bidirectional"))
      (node (ref "IC3") (pin "8") (pinfunction "GNDIO_8") (pintype "bidirectional"))
      (node (ref "IC3") (pin "9") (pinfunction "GND_9") (pintype "bidirectional"))
      (node (ref "IC9") (pin "B1") (pinfunction "VSEL_B1") (pintype "bidirectional"))
      (node (ref "IC9") (pin "C1") (pinfunction "AGND_C1") (pintype "bidirectional"))
      (node (ref "IC9") (pin "C2") (pinfunction "PGND_1_C2") (pintype "bidirectional"))
      (node (ref "IC9") (pin "C3") (pinfunction "PGND_2_C3") (pintype "bidirectional"))
      (node (ref "J2") (pin "3") (pinfunction "3_3") (pintype "bidirectional"))
      (node (ref "J2") (pin "5") (pinfunction "5_5") (pintype "bidirectional"))
      (node (ref "J4") (pin "A12_B1") (pinfunction "GND_A12_B1") (pintype "power_in"))
      (node (ref "J4") (pin "A1_B12") (pinfunction "GND_A1_B12") (pintype "power_in"))
      (node (ref "J4") (pin "SH1") (pinfunction "SHIELD_SH1") (pintype "passive"))
      (node (ref "J4") (pin "SH2") (pinfunction "SHIELD_SH2") (pintype "passive"))
      (node (ref "J4") (pin "SH3") (pinfunction "SHIELD_SH3") (pintype "passive"))
      (node (ref "J4") (pin "SH4") (pinfunction "SHIELD_SH4") (pintype "passive"))
      (node (ref "J5") (pin "17") (pinfunction "17_17") (pintype "bidirectional"))
      (node (ref "J5") (pin "8") (pinfunction "8_8") (pintype "bidirectional"))
      (node (ref "J5") (pin "MP1") (pinfunction "MP1_MP1") (pintype "bidirectional"))
      (node (ref "J5") (pin "MP2") (pinfunction "MP2_MP2") (pintype "bidirectional"))
      (node (ref "R1_USB") (pin "1") (pinfunction "1_1") (pintype "bidirectional"))
      (node (ref "R2-USB1") (pin "2") (pinfunction "2_2") (pintype "bidirectional"))
      (node (ref "R2_EP_DR") (pin "1") (pinfunction "1_1") (pintype "bidirectional"))
      (node (ref "R3") (pin "1") (pinfunction "1_1") (pintype "bidirectional"))
      (node (ref "R9") (pin "1") (pinfunction "1_1") (pintype "bidirectional"))
      (node (ref "R_TYPE_SEL") (pin "1") (pinfunction "1_1") (pintype "bidirectional"))
      (node (ref "SJ1") (pin "1") (pinfunction "1_1") (pintype "passive"))
      (node (ref "SW_DN1") (pin "1") (pinfunction "1_1") (pintype "passive"))
      (node (ref "SW_ENT1") (pin "1") (pinfunction "1_1") (pintype "passive"))
      (node (ref "SW_UP1") (pin "1") (pinfunction "1_1") (pintype "passive"))
      (node (ref "TP_BAT_GND1") (pin "TP") (pinfunction "TP_TP") (pintype "input"))
      (node (ref "TP_GND") (pin "TP") (pinfunction "TP_TP") (pintype "input"))
      (node (ref "U1") (pin "P$74") (pinfunction "VSS_PAD_P$74") (pintype "bidirectional"))
      (node (ref "U1") (pin "P$75") (pinfunction "VSS_PAD_P$75") (pintype "bidirectional"))
      (node (ref "U1") (pin "P$76") (pinfunction "VSS_PAD_P$76") (pintype "bidirectional"))
      (node (ref "U1") (pin "P$77") (pinfunction "VSS_PAD_P$77") (pintype "bidirectional"))
      (node (ref "U1") (pin "P$78") (pinfunction "VSS_PAD_P$78") (pintype "bidirectional"))
      (node (ref "U1") (pin "P$79") (pinfunction "VSS_PAD_P$79") (pintype "bidirectional"))
      (node (ref "U1") (pin "P$80") (pinfunction "VSS_PAD_P$80") (pintype "bidirectional"))
      (node (ref "U1") (pin "P$81") (pinfunction "VSS_PAD_P$81") (pintype "bidirectional"))
      (node (ref "U1") (pin "P$82") (pinfunction "VSS_PAD_P$82") (pintype "bidirectional"))
      (node (ref "U1") (pin "P$83") (pinfunction "VSS_PAD_P$83") (pintype "bidirectional"))
      (node (ref "U1") (pin "P$84") (pinfunction "VSS_PAD_P$84") (pintype "bidirectional"))
      (node (ref "U1") (pin "P$85") (pinfunction "VSS_PAD_P$85") (pintype "bidirectional"))
      (node (ref "U1") (pin "P$86") (pinfunction "VSS_PAD_P$86") (pintype "bidirectional"))
      (node (ref "U1") (pin "P$87") (pinfunction "VSS_PAD_P$87") (pintype "bidirectional"))
      (node (ref "U1") (pin "P$88") (pinfunction "VSS_PAD_P$88") (pintype "bidirectional"))
      (node (ref "U1") (pin "P$89") (pinfunction "VSS_PAD_P$89") (pintype "bidirectional"))
      (node (ref "U1") (pin "P$90") (pinfunction "VSS_PAD_P$90") (pintype "bidirectional"))
      (node (ref "U1") (pin "P$B7") (pinfunction "VSS_P$B7") (pintype "power_in"))
      (node (ref "U1") (pin "P$F23") (pinfunction "VSS_PA_P$F23") (pintype "bidirectional"))
      (node (ref "U3") (pin "1") (pinfunction "CTG_1") (pintype "power_in"))
      (node (ref "U3") (pin "4") (pinfunction "GND_4") (pintype "power_in"))
      (node (ref "U3") (pin "6") (pinfunction "QSTRT_6") (pintype "input"))
      (node (ref "U3") (pin "9") (pinfunction "EP_9") (pintype "power_in"))
      (node (ref "X1") (pin "2") (pinfunction "2_2") (pintype "passive"))
      (node (ref "X1") (pin "4") (pinfunction "4_4") (pintype "passive"))
    )
    (net (code "15") (name "HAPTIC_EN") (class "Default")
      (node (ref "U1") (pin "P$U1") (pinfunction "P0.12_P$U1") (pintype "bidirectional"))
    )
    (net (code "16") (name "HAPTIC_EN{slash}1.4C") (class "Default")
      (node (ref "IC2") (pin "A1") (pinfunction "EN_A1") (pintype "bidirectional"))
    )
    (net (code "17") (name "IMU_INT1") (class "Default")
      (node (ref "IC3") (pin "5") (pinfunction "INT1_5") (pintype "bidirectional"))
      (node (ref "U1") (pin "P$N1") (pinfunction "P0.08_P$N1") (pintype "bidirectional"))
    )
    (net (code "18") (name "IMU_INT2") (class "Default")
      (node (ref "IC3") (pin "6") (pinfunction "INT2_6") (pintype "bidirectional"))
      (node (ref "U1") (pin "P$P2") (pinfunction "P1.08_P$P2") (pintype "bidirectional"))
    )
    (net (code "19") (name "LX1") (class "Default")
      (node (ref "IC9") (pin "B2") (pinfunction "SW1_1_B2") (pintype "bidirectional"))
      (node (ref "IC9") (pin "B3") (pinfunction "SW1_2_B3") (pintype "bidirectional"))
      (node (ref "L7") (pin "1") (pinfunction "1_1") (pintype "bidirectional"))
    )
    (net (code "20") (name "LX2") (class "Default")
      (node (ref "IC9") (pin "D2") (pinfunction "SW2_1_D2") (pintype "bidirectional"))
      (node (ref "IC9") (pin "D3") (pinfunction "SW2_2_D3") (pintype "bidirectional"))
      (node (ref "L7") (pin "2") (pinfunction "2_2") (pintype "bidirectional"))
    )
    (net (code "21") (name "MOSI") (class "Default")
      (node (ref "J5") (pin "14") (pinfunction "14_14") (pintype "bidirectional"))
      (node (ref "U1") (pin "P$B13") (pinfunction "P0.03/AIN1_P$B13") (pintype "bidirectional"))
    )
    (net (code "22") (name "N$22") (class "Default")
      (node (ref "R17") (pin "1") (pinfunction "1_1") (pintype "bidirectional"))
      (node (ref "R18") (pin "1") (pinfunction "1_1") (pintype "bidirectional"))
    )
    (net (code "23") (name "Net-(ANT1-FEED)") (class "Default")
      (node (ref "ANT1") (pin "1") (pinfunction "FEED_1") (pintype "input"))
      (node (ref "C22") (pin "1") (pinfunction "1_1") (pintype "passive"))
      (node (ref "C4") (pin "1") (pinfunction "1_1") (pintype "passive"))
      (node (ref "L1") (pin "2") (pinfunction "2_2") (pintype "bidirectional"))
    )
    (net (code "24") (name "Net-(D2-K)") (class "Default")
      (node (ref "C2-EP-DR") (pin "1") (pinfunction "1_1") (pintype "passive"))
      (node (ref "D2") (pin "1") (pinfunction "K_1") (pintype "bidirectional"))
      (node (ref "D4") (pin "2") (pinfunction "A_2") (pintype "bidirectional"))
    )
    (net (code "25") (name "Net-(D5-A)") (class "Default")
      (node (ref "C2-EP-DR") (pin "2") (pinfunction "2_2") (pintype "passive"))
      (node (ref "D5") (pin "2") (pinfunction "A_2") (pintype "bidirectional"))
      (node (ref "L5") (pin "1") (pinfunction "1_1") (pintype "passive"))
      (node (ref "Q3") (pin "3") (pinfunction "D_3") (pintype "bidirectional"))
    )
    (net (code "26") (name "Net-(EPD_C1-Pad2)") (class "Default")
      (node (ref "EPD_C1") (pin "2") (pinfunction "2_2") (pintype "passive"))
      (node (ref "J5") (pin "4") (pinfunction "4_4") (pintype "bidirectional"))
    )
    (net (code "27") (name "Net-(EPD_C2-Pad2)") (class "Default")
      (node (ref "EPD_C2") (pin "2") (pinfunction "2_2") (pintype "passive"))
      (node (ref "J5") (pin "3") (pinfunction "3_3") (pintype "bidirectional"))
    )
    (net (code "28") (name "Net-(EPD_C6-Pad2)") (class "Default")
      (node (ref "EPD_C6") (pin "2") (pinfunction "2_2") (pintype "passive"))
      (node (ref "J5") (pin "18") (pinfunction "18_18") (pintype "bidirectional"))
    )
    (net (code "29") (name "Net-(EPD_C7-Pad2)") (class "Default")
      (node (ref "EPD_C7") (pin "2") (pinfunction "2_2") (pintype "passive"))
      (node (ref "J5") (pin "19") (pinfunction "19_19") (pintype "bidirectional"))
    )
    (net (code "30") (name "Net-(EPD_C8-Pad2)") (class "Default")
      (node (ref "EPD_C8") (pin "2") (pinfunction "2_2") (pintype "passive"))
      (node (ref "J5") (pin "20") (pinfunction "20_20") (pintype "bidirectional"))
    )
    (net (code "31") (name "Net-(EPD_C10-Pad2)") (class "Default")
      (node (ref "EPD_C10") (pin "2") (pinfunction "2_2") (pintype "passive"))
      (node (ref "J5") (pin "22") (pinfunction "22_22") (pintype "bidirectional"))
    )
    (net (code "32") (name "Net-(EPD_C12-Pad2)") (class "Default")
      (node (ref "EPD_C12") (pin "2") (pinfunction "2_2") (pintype "passive"))
      (node (ref "J5") (pin "24") (pinfunction "24_24") (pintype "bidirectional"))
    )
    (net (code "33") (name "Net-(IC1-TS{slash}MR)") (class "Default")
      (node (ref "IC1") (pin "D1") (pinfunction "TS/MR_D1") (pintype "bidirectional"))
      (node (ref "R9") (pin "2") (pinfunction "2_2") (pintype "bidirectional"))
    )
    (net (code "34") (name "Net-(IC2-REG)") (class "Default")
      (node (ref "C32") (pin "1") (pinfunction "1_1") (pintype "passive"))
      (node (ref "IC2") (pin "A2") (pinfunction "REG_A2") (pintype "bidirectional"))
    )
    (net (code "35") (name "Net-(IC3-SDO)") (class "Default")
      (node (ref "IC3") (pin "1") (pinfunction "SDO_1") (pintype "bidirectional"))
      (node (ref "R3") (pin "2") (pinfunction "2_2") (pintype "bidirectional"))
    )
    (net (code "36") (name "Net-(IC9-SCL)") (class "Default")
      (node (ref "IC9") (pin "D1") (pinfunction "SCL_D1") (pintype "bidirectional"))
      (node (ref "R4") (pin "2") (pinfunction "2_2") (pintype "bidirectional"))
    )
    (net (code "37") (name "Net-(IC9-SDA)") (class "Default")
      (node (ref "IC9") (pin "E1") (pinfunction "SDA_E1") (pintype "bidirectional"))
      (node (ref "R2") (pin "2") (pinfunction "2_2") (pintype "bidirectional"))
    )
    (net (code "38") (name "Net-(J4-CC1)") (class "Default")
      (node (ref "J4") (pin "A5") (pinfunction "CC1_A5") (pintype "bidirectional"))
      (node (ref "R1_USB") (pin "2") (pinfunction "2_2") (pintype "bidirectional"))
    )
    (net (code "39") (name "Net-(J4-CC2)") (class "Default")
      (node (ref "J4") (pin "B5") (pinfunction "CC2_B5") (pintype "bidirectional"))
      (node (ref "R2-USB1") (pin "1") (pinfunction "1_1") (pintype "bidirectional"))
    )
    (net (code "40") (name "Net-(L2-Pad2)") (class "Default")
      (node (ref "L2") (pin "2") (pinfunction "2_2") (pintype "passive"))
      (node (ref "L3") (pin "1") (pinfunction "1_1") (pintype "passive"))
    )
    (net (code "41") (name "Net-(R1_EP_DR-Pad1)") (class "Default")
      (node (ref "R1_EP_DR") (pin "1") (pinfunction "1_1") (pintype "bidirectional"))
      (node (ref "R_TYPE_SEL") (pin "2") (pinfunction "2_2") (pintype "bidirectional"))
      (node (ref "SJ1") (pin "2") (pinfunction "2_2") (pintype "passive"))
    )
    (net (code "42") (name "Net-(U1-ANT)") (class "Default")
      (node (ref "C3") (pin "1") (pinfunction "1_1") (pintype "passive"))
      (node (ref "L1") (pin "1") (pinfunction "1_1") (pintype "bidirectional"))
      (node (ref "U1") (pin "P$H23") (pinfunction "ANT_P$H23") (pintype "bidirectional"))
    )
    (net (code "43") (name "Net-(U1-DCC)") (class "Default")
      (node (ref "L2") (pin "1") (pinfunction "1_1") (pintype "passive"))
      (node (ref "U1") (pin "P$B3") (pinfunction "DCC_P$B3") (pintype "output"))
    )
    (net (code "44") (name "Net-(U1-DEC1)") (class "Default")
      (node (ref "C5") (pin "1") (pinfunction "1_1") (pintype "passive"))
      (node (ref "U1") (pin "P$C1") (pinfunction "DEC1_P$C1") (pintype "power_in"))
    )
    (net (code "45") (name "Net-(U1-DEC2)") (class "Default")
      (node (ref "C13") (pin "1") (pinfunction "1_1") (pintype "passive"))
      (node (ref "U1") (pin "P$A18") (pinfunction "DEC2_P$A18") (pintype "bidirectional"))
    )
    (net (code "46") (name "Net-(U1-DEC3)") (class "Default")
      (node (ref "C11") (pin "1") (pinfunction "1_1") (pintype "passive"))
      (node (ref "U1") (pin "P$D23") (pinfunction "DEC3_P$D23") (pintype "bidirectional"))
    )
    (net (code "47") (name "Net-(U1-DEC3V3)") (class "Default")
      (node (ref "C20") (pin "1") (pinfunction "1_1") (pintype "passive"))
      (node (ref "U1") (pin "P$AC5") (pinfunction "DEC3V3_P$AC5") (pintype "bidirectional"))
    )
    (net (code "48") (name "Net-(U1-DEC4)") (class "Default")
      (node (ref "C10") (pin "1") (pinfunction "1_1") (pintype "passive"))
      (node (ref "C15") (pin "1") (pinfunction "1_1") (pintype "passive"))
      (node (ref "C16") (pin "1") (pinfunction "1_1") (pintype "passive"))
      (node (ref "L3") (pin "2") (pinfunction "2_2") (pintype "passive"))
      (node (ref "U1") (pin "P$B5") (pinfunction "DEC4_P$B5") (pintype "power_in"))
      (node (ref "U1") (pin "P$E24") (pinfunction "DEC6_P$E24") (pintype "bidirectional"))
    )
    (net (code "49") (name "Net-(U1-DEC5)") (class "Default")
      (node (ref "C9") (pin "1") (pinfunction "1_1") (pintype "passive"))
      (node (ref "U1") (pin "P$N24") (pinfunction "DEC5_P$N24") (pintype "bidirectional"))
    )
    (net (code "50") (name "Net-(U1-P0.00{slash}XL1)") (class "Default")
      (node (ref "C17") (pin "2") (pinfunction "2_2") (pintype "passive"))
      (node (ref "U1") (pin "P$D2") (pinfunction "P0.00/XL1_P$D2") (pintype "bidirectional"))
      (node (ref "X2") (pin "2") (pinfunction "2_2") (pintype "passive"))
    )
    (net (code "51") (name "Net-(U1-P0.01{slash}XL2)") (class "Default")
      (node (ref "C18") (pin "2") (pinfunction "2_2") (pintype "passive"))
      (node (ref "U1") (pin "P$F2") (pinfunction "P0.01/XL2_P$F2") (pintype "bidirectional"))
      (node (ref "X2") (pin "1") (pinfunction "1_1") (pintype "passive"))
    )
    (net (code "52") (name "Net-(U1-XC1)") (class "Default")
      (node (ref "C1") (pin "1") (pinfunction "1_1") (pintype "passive"))
      (node (ref "U1") (pin "P$B24") (pinfunction "XC1_P$B24") (pintype "input"))
      (node (ref "X1") (pin "1") (pinfunction "1_1") (pintype "passive"))
    )
    (net (code "53") (name "Net-(U1-XC2)") (class "Default")
      (node (ref "C2") (pin "1") (pinfunction "1_1") (pintype "passive"))
      (node (ref "U1") (pin "P$A23") (pinfunction "XC2_P$A23") (pintype "output"))
      (node (ref "X1") (pin "3") (pinfunction "3_3") (pintype "passive"))
    )
    (net (code "54") (name "OUT+") (class "Default")
      (node (ref "IC2") (pin "A3") (pinfunction "OUT+_A3") (pintype "bidirectional"))
      (node (ref "TP_OP") (pin "TP") (pinfunction "TP_TP") (pintype "input"))
    )
    (net (code "55") (name "OUT-") (class "Default")
      (node (ref "IC2") (pin "C3") (pinfunction "OUT-_C3") (pintype "bidirectional"))
      (node (ref "TP_ON") (pin "TP") (pinfunction "TP_TP") (pintype "input"))
    )
    (net (code "56") (name "P0.04") (class "Default")
      (node (ref "U1") (pin "P$J1") (pinfunction "P0.04/AIN2_P$J1") (pintype "bidirectional"))
    )
    (net (code "57") (name "P0.09") (class "Default")
      (node (ref "U1") (pin "P$L24") (pinfunction "P0.09/NFC1_P$L24") (pintype "bidirectional"))
    )
    (net (code "58") (name "P0.13") (class "Default")
      (node (ref "C29") (pin "1") (pinfunction "1_1") (pintype "passive"))
      (node (ref "C30") (pin "1") (pinfunction "1_1") (pintype "passive"))
      (node (ref "C31") (pin "1") (pinfunction "1_1") (pintype "passive"))
      (node (ref "R5") (pin "1") (pinfunction "1_1") (pintype "bidirectional"))
      (node (ref "R7") (pin "1") (pinfunction "1_1") (pintype "bidirectional"))
      (node (ref "R8") (pin "1") (pinfunction "1_1") (pintype "bidirectional"))
      (node (ref "SW_DN1") (pin "2") (pinfunction "2_2") (pintype "passive"))
      (node (ref "SW_ENT1") (pin "2") (pinfunction "2_2") (pintype "passive"))
      (node (ref "SW_UP1") (pin "2") (pinfunction "2_2") (pintype "passive"))
      (node (ref "U1") (pin "P$AD8") (pinfunction "P0.13_P$AD8") (pintype "bidirectional"))
    )
    (net (code "59") (name "P0.14") (class "Default")
      (node (ref "U1") (pin "P$AC9") (pinfunction "P0.14_P$AC9") (pintype "bidirectional"))
    )
    (net (code "60") (name "P0.19") (class "Default")
      (node (ref "U1") (pin "P$AC15") (pinfunction "P0.19_P$AC15") (pintype "bidirectional"))
    )
    (net (code "61") (name "P0.20") (class "Default")
      (node (ref "U1") (pin "P$AD16") (pinfunction "P0.20_P$AD16") (pintype "bidirectional"))
    )
    (net (code "62") (name "P0.21") (class "Default")
      (node (ref "U1") (pin "P$AC17") (pinfunction "P0.21_P$AC17") (pintype "bidirectional"))
    )
    (net (code "63") (name "P0.22") (class "Default")
      (node (ref "U1") (pin "P$AD18") (pinfunction "P0.22_P$AD18") (pintype "bidirectional"))
    )
    (net (code "64") (name "P0.23") (class "Default")
      (node (ref "U1") (pin "P$AC19") (pinfunction "P0.23_P$AC19") (pintype "bidirectional"))
    )
    (net (code "65") (name "P0.24") (class "Default")
      (node (ref "U1") (pin "P$AD20") (pinfunction "P0.24_P$AD20") (pintype "bidirectional"))
    )
    (net (code "66") (name "P0.25") (class "Default")
      (node (ref "U1") (pin "P$AC21") (pinfunction "P0.25_P$AC21") (pintype "bidirectional"))
    )
    (net (code "67") (name "P0.26") (class "Default")
      (node (ref "U1") (pin "P$AD22") (pinfunction "P1.00_P$AD22") (pintype "bidirectional"))
      (node (ref "U1") (pin "P$G1") (pinfunction "P0.26_P$G1") (pintype "bidirectional"))
    )
    (net (code "68") (name "P0.27") (class "Default")
      (node (ref "U1") (pin "P$H2") (pinfunction "P0.27_P$H2") (pintype "bidirectional"))
    )
    (net (code "69") (name "P0.28") (class "Default")
      (node (ref "U1") (pin "P$B11") (pinfunction "P0.28/AIN4_P$B11") (pintype "bidirectional"))
    )
    (net (code "70") (name "P0.29") (class "Default")
      (node (ref "U1") (pin "P$A10") (pinfunction "P0.29/AIN5_P$A10") (pintype "bidirectional"))
    )
    (net (code "71") (name "P0.30") (class "Default")
      (node (ref "U1") (pin "P$B9") (pinfunction "P0.30/AIN6_P$B9") (pintype "bidirectional"))
    )
    (net (code "72") (name "P0.31") (class "Default")
      (node (ref "U1") (pin "P$A8") (pinfunction "P0.31/AIN7_P$A8") (pintype "bidirectional"))
    )
    (net (code "73") (name "P1.01") (class "Default")
      (node (ref "Q1") (pin "1") (pinfunction "G_1") (pintype "bidirectional"))
      (node (ref "R_PWR_EPD1") (pin "1") (pinfunction "1_1") (pintype "bidirectional"))
      (node (ref "U1") (pin "P$Y23") (pinfunction "P1.01_P$Y23") (pintype "bidirectional"))
    )
    (net (code "74") (name "P1.02") (class "Default")
      (node (ref "U1") (pin "P$W24") (pinfunction "P1.02_P$W24") (pintype "bidirectional"))
    )
    (net (code "75") (name "P1.03") (class "Default")
      (node (ref "U1") (pin "P$V23") (pinfunction "P1.03_P$V23") (pintype "bidirectional"))
    )
    (net (code "76") (name "P1.04") (class "Default")
      (node (ref "U1") (pin "P$U24") (pinfunction "P1.04_P$U24") (pintype "bidirectional"))
    )
    (net (code "77") (name "P1.05") (class "Default")
      (node (ref "U1") (pin "P$T23") (pinfunction "P1.05_P$T23") (pintype "bidirectional"))
    )
    (net (code "78") (name "P1.06") (class "Default")
      (node (ref "U1") (pin "P$R24") (pinfunction "P1.06_P$R24") (pintype "bidirectional"))
    )
    (net (code "79") (name "P1.07") (class "Default")
      (node (ref "U1") (pin "P$P23") (pinfunction "P1.07_P$P23") (pintype "bidirectional"))
    )
    (net (code "80") (name "P1.09") (class "Default")
      (node (ref "U1") (pin "P$R1") (pinfunction "P1.09_P$R1") (pintype "bidirectional"))
    )
    (net (code "81") (name "P1.10") (class "Default")
      (node (ref "U1") (pin "P$A20") (pinfunction "P1.10_P$A20") (pintype "bidirectional"))
    )
    (net (code "82") (name "P1.11") (class "Default")
      (node (ref "U1") (pin "P$B19") (pinfunction "P1.11_P$B19") (pintype "bidirectional"))
    )
    (net (code "83") (name "P1.12") (class "Default")
      (node (ref "U1") (pin "P$B17") (pinfunction "P1.12_P$B17") (pintype "bidirectional"))
    )
    (net (code "84") (name "P1.13") (class "Default")
      (node (ref "U1") (pin "P$A16") (pinfunction "P1.13_P$A16") (pintype "bidirectional"))
    )
    (net (code "85") (name "P1.14") (class "Default")
      (node (ref "U1") (pin "P$B15") (pinfunction "P1.14_P$B15") (pintype "bidirectional"))
    )
    (net (code "86") (name "P1.15") (class "Default")
      (node (ref "U1") (pin "P$A14") (pinfunction "P1.15_P$A14") (pintype "bidirectional"))
    )
    (net (code "87") (name "PMIC_INT") (class "Default")
      (node (ref "IC1") (pin "A1") (pinfunction "~{INT}_A1") (pintype "bidirectional"))
      (node (ref "U1") (pin "P$T2") (pinfunction "P0.11_P$T2") (pintype "bidirectional"))
    )
    (net (code "88") (name "PREVGH") (class "Default")
      (node (ref "D5") (pin "1") (pinfunction "K_1") (pintype "bidirectional"))
      (node (ref "EPD_C9") (pin "2") (pinfunction "2_2") (pintype "passive"))
      (node (ref "J5") (pin "21") (pinfunction "21_21") (pintype "bidirectional"))
    )
    (net (code "89") (name "PREVGL") (class "Default")
      (node (ref "D2") (pin "2") (pinfunction "A_2") (pintype "bidirectional"))
      (node (ref "EPD_C11") (pin "2") (pinfunction "2_2") (pintype "passive"))
      (node (ref "J5") (pin "23") (pinfunction "23_23") (pintype "bidirectional"))
    )
    (net (code "90") (name "RESE") (class "Default")
      (node (ref "J5") (pin "2") (pinfunction "2_2") (pintype "bidirectional"))
      (node (ref "Q3") (pin "2") (pinfunction "S_2") (pintype "bidirectional"))
      (node (ref "R1_EP_DR") (pin "2") (pinfunction "2_2") (pintype "bidirectional"))
    )
    (net (code "91") (name "RESET") (class "Default")
      (node (ref "J2") (pin "6") (pinfunction "6_6") (pintype "bidirectional"))
      (node (ref "TP_RESET") (pin "TP") (pinfunction "TP_TP") (pintype "input"))
      (node (ref "U1") (pin "P$AC13") (pinfunction "P0.18/RESET_P$AC13") (pintype "bidirectional"))
    )
    (net (code "92") (name "SCK") (class "Default")
      (node (ref "J5") (pin "13") (pinfunction "13_13") (pintype "bidirectional"))
      (node (ref "U1") (pin "P$A12") (pinfunction "P0.02/AIN0_P$A12") (pintype "bidirectional"))
    )
    (net (code "93") (name "SCL") (class "Default")
      (node (ref "IC1") (pin "B1") (pinfunction "SCL_B1") (pintype "bidirectional"))
      (node (ref "IC2") (pin "C1") (pinfunction "SCL_C1") (pintype "bidirectional"))
      (node (ref "IC3") (pin "12") (pinfunction "SCX_12") (pintype "bidirectional"))
      (node (ref "R17") (pin "2") (pinfunction "2_2") (pintype "bidirectional"))
      (node (ref "R4") (pin "1") (pinfunction "1_1") (pintype "bidirectional"))
      (node (ref "TP_SCL") (pin "TP") (pinfunction "TP_TP") (pintype "input"))
      (node (ref "U1") (pin "P$M2") (pinfunction "P0.07_P$M2") (pintype "bidirectional"))
      (node (ref "U3") (pin "7") (pinfunction "SCL_7") (pintype "input"))
    )
    (net (code "94") (name "SDA") (class "Default")
      (node (ref "IC1") (pin "C1") (pinfunction "SDA_C1") (pintype "bidirectional"))
      (node (ref "IC3") (pin "2") (pinfunction "SDX_2") (pintype "bidirectional"))
      (node (ref "R18") (pin "2") (pinfunction "2_2") (pintype "bidirectional"))
      (node (ref "R2") (pin "1") (pinfunction "1_1") (pintype "bidirectional"))
      (node (ref "TP_SDA") (pin "TP") (pinfunction "TP_TP") (pintype "input"))
      (node (ref "U1") (pin "P$L1") (pinfunction "P0.06_P$L1") (pintype "bidirectional"))
      (node (ref "U3") (pin "8") (pinfunction "SDA_8") (pintype "bidirectional"))
    )
    (net (code "95") (name "SDA{slash}1.4C") (class "Default")
      (node (ref "IC2") (pin "B2") (pinfunction "SDA_B2") (pintype "bidirectional"))
    )
    (net (code "96") (name "SWDCLK") (class "Default")
      (node (ref "J2") (pin "4") (pinfunction "4_4") (pintype "bidirectional"))
      (node (ref "TP_SWDCLK") (pin "TP") (pinfunction "TP_TP") (pintype "input"))
      (node (ref "U1") (pin "P$AA24") (pinfunction "SWDCLK_P$AA24") (pintype "input"))
    )
    (net (code "97") (name "SWDIO") (class "Default")
      (node (ref "J2") (pin "2") (pinfunction "2_2") (pintype "bidirectional"))
      (node (ref "TP_SWDIO") (pin "TP") (pinfunction "TP_TP") (pintype "input"))
      (node (ref "U1") (pin "P$AC24") (pinfunction "SWDIO_P$AC24") (pintype "bidirectional"))
    )
    (net (code "98") (name "SWO") (class "Default")
      (node (ref "TP_SWO") (pin "TP") (pinfunction "TP_TP") (pintype "input"))
    )
    (net (code "99") (name "VBAT") (class "Default")
      (node (ref "C27") (pin "1") (pinfunction "1_1") (pintype "passive"))
      (node (ref "C37") (pin "1") (pinfunction "1_1") (pintype "passive"))
      (node (ref "IC1") (pin "C2") (pinfunction "BAT_C2") (pintype "bidirectional"))
      (node (ref "TP_VBAT1") (pin "TP") (pinfunction "TP_TP") (pintype "input"))
      (node (ref "U3") (pin "2") (pinfunction "CELL_2") (pintype "power_in"))
      (node (ref "U3") (pin "3") (pinfunction "VDD_3") (pintype "power_in"))
    )
    (net (code "100") (name "VBUS") (class "Default")
      (node (ref "C21") (pin "1") (pinfunction "1_1") (pintype "passive"))
      (node (ref "C38") (pin "1") (pinfunction "1_1") (pintype "passive"))
      (node (ref "C42") (pin "1") (pinfunction "1_1") (pintype "passive"))
      (node (ref "C43") (pin "1") (pinfunction "1_1") (pintype "passive"))
      (node (ref "D3") (pin "5") (pinfunction "VBUS_5") (pintype "bidirectional"))
      (node (ref "IC1") (pin "A2") (pinfunction "IN_A2") (pintype "bidirectional"))
      (node (ref "J4") (pin "A4_B9") (pinfunction "VBUS_A4_B9") (pintype "power_in"))
      (node (ref "J4") (pin "A9_B4") (pinfunction "VBUS_A9_B4") (pintype "power_in"))
      (node (ref "U1") (pin "P$AD2") (pinfunction "VBUS_P$AD2") (pintype "power_in"))
    )
    (net (code "101") (name "VREG") (class "Default")
      (node (ref "C23") (pin "2") (pinfunction "2_2") (pintype "passive"))
      (node (ref "C24") (pin "2") (pinfunction "2_2") (pintype "passive"))
      (node (ref "C39") (pin "1") (pinfunction "1_1") (pintype "passive"))
      (node (ref "IC1") (pin "B2") (pinfunction "SYS_B2") (pintype "bidirectional"))
      (node (ref "IC9") (pin "A1") (pinfunction "EN_A1") (pintype "bidirectional"))
      (node (ref "IC9") (pin "A2") (pinfunction "VIN_1_A2") (pintype "bidirectional"))
      (node (ref "IC9") (pin "A3") (pinfunction "VIN_2_A3") (pintype "bidirectional"))
      (node (ref "TP_VREG") (pin "TP") (pinfunction "TP_TP") (pintype "input"))
    )
    (net (code "102") (name "unconnected-(ANT1-NC-Pad2)") (class "Default")
      (node (ref "ANT1") (pin "2") (pinfunction "NC_2") (pintype "no_connect"))
    )
    (net (code "103") (name "unconnected-(IC3-ASCL-Pad11)") (class "Default")
      (node (ref "IC3") (pin "11") (pinfunction "ASCL_11") (pintype "bidirectional"))
    )
    (net (code "104") (name "unconnected-(IC3-ASDA-Pad4)") (class "Default")
      (node (ref "IC3") (pin "4") (pinfunction "ASDA_4") (pintype "bidirectional"))
    )
    (net (code "105") (name "unconnected-(J4-SBU1-PadA8)") (class "Default")
      (node (ref "J4") (pin "A8") (pinfunction "SBU1_A8") (pintype "bidirectional"))
    )
    (net (code "106") (name "unconnected-(J4-SBU2-PadB8)") (class "Default")
      (node (ref "J4") (pin "B8") (pinfunction "SBU2_B8") (pintype "bidirectional"))
    )
    (net (code "107") (name "unconnected-(J5-Pad5)") (class "Default")
      (node (ref "J5") (pin "5") (pinfunction "5_5") (pintype "bidirectional"))
    )
    (net (code "108") (name "unconnected-(J5-Pad6)") (class "Default")
      (node (ref "J5") (pin "6") (pinfunction "6_6") (pintype "bidirectional"))
    )
    (net (code "109") (name "unconnected-(J5-Pad7)") (class "Default")
      (node (ref "J5") (pin "7") (pinfunction "7_7") (pintype "bidirectional"))
    )
    (net (code "110") (name "unconnected-(U1-DCCH-PadP$AB2)") (class "Default")
      (node (ref "U1") (pin "P$AB2") (pinfunction "DCCH_P$AB2") (pintype "bidirectional"))
    )
  )
)
